# Trefferzonenmodul.net
KiCad netlist of a schematic drawn in EAGLE
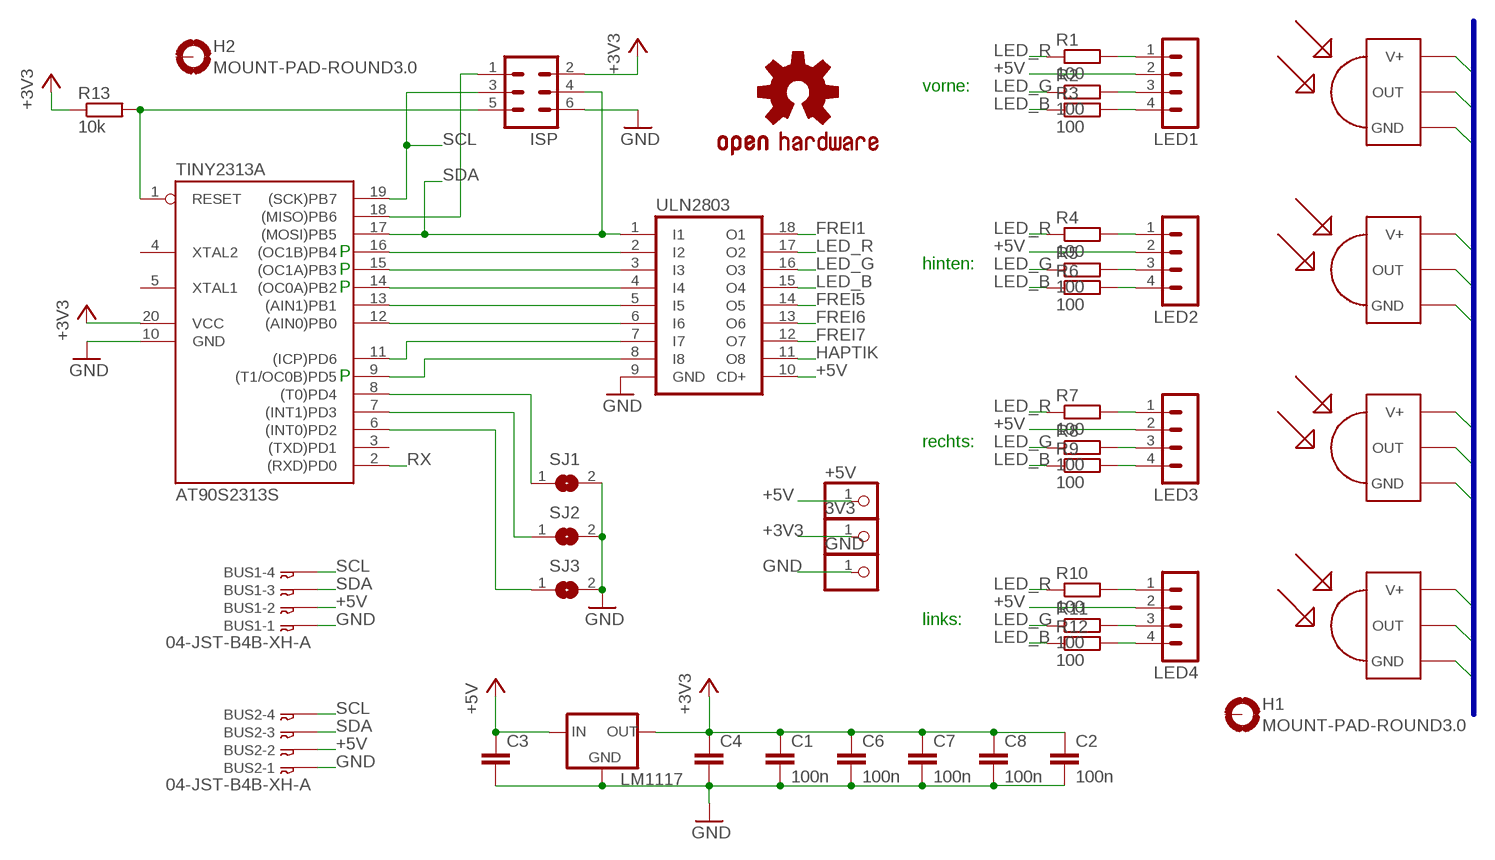
[diagram p0: schematic, sheet 1]

(export (version "E")
  (design (tool "Eeschema 10.0.6"))
  (components
    (comp (ref "+5V")
      (value "PINHD-1X1")
      (footprint "eagle-import:1X01")
      (libsource (lib "eagle-import") (part "PINHD-1X1"))
    )
    (comp (ref "3V3")
      (value "PINHD-1X1")
      (footprint "eagle-import:1X01")
      (libsource (lib "eagle-import") (part "PINHD-1X1"))
    )
    (comp (ref "BUS1")
      (value "04-JST-B4B-XH-A")
      (footprint "eagle-import:B4B-XH")
      (libsource (lib "eagle-import") (part "04-JST-B4B-XH-A"))
    )
    (comp (ref "BUS2")
      (value "04-JST-B4B-XH-A")
      (footprint "eagle-import:B4B-XH")
      (libsource (lib "eagle-import") (part "04-JST-B4B-XH-A"))
    )
    (comp (ref "C1")
      (value "100n")
      (footprint "eagle-import:C0805")
      (libsource (lib "eagle-import") (part "C-EUC0805"))
    )
    (comp (ref "C2")
      (value "100n")
      (footprint "eagle-import:C0805")
      (libsource (lib "eagle-import") (part "C-EUC0805"))
    )
    (comp (ref "C3")
      (value "C-EUCAP_UNIVERSAL")
      (footprint "eagle-import:C1808")
      (libsource (lib "eagle-import") (part "C-EUCAP_UNIVERSAL"))
    )
    (comp (ref "C4")
      (value "C-EUCAP_UNIVERSAL")
      (footprint "eagle-import:C1808")
      (libsource (lib "eagle-import") (part "C-EUCAP_UNIVERSAL"))
    )
    (comp (ref "C6")
      (value "100n")
      (footprint "eagle-import:C0805")
      (libsource (lib "eagle-import") (part "C-EUC0805"))
    )
    (comp (ref "C7")
      (value "100n")
      (footprint "eagle-import:C0805")
      (libsource (lib "eagle-import") (part "C-EUC0805"))
    )
    (comp (ref "C8")
      (value "100n")
      (footprint "eagle-import:C0805")
      (libsource (lib "eagle-import") (part "C-EUC0805"))
    )
    (comp (ref "GND")
      (value "PINHD-1X1")
      (footprint "eagle-import:1X01")
      (libsource (lib "eagle-import") (part "PINHD-1X1"))
    )
    (comp (ref "H1")
      (value "MOUNT-PAD-ROUND3.0")
      (footprint "eagle-import:3,0-PAD")
      (libsource (lib "eagle-import") (part "MOUNT-PAD-ROUND3.0"))
    )
    (comp (ref "H2")
      (value "MOUNT-PAD-ROUND3.0")
      (footprint "eagle-import:3,0-PAD")
      (libsource (lib "eagle-import") (part "MOUNT-PAD-ROUND3.0"))
    )
    (comp (ref "ISP")
      (value "MA03-2")
      (footprint "eagle-import:MA03-2")
      (libsource (lib "eagle-import") (part "MA03-2"))
    )
    (comp (ref "LED1")
      (value "MA04-1")
      (footprint "eagle-import:MA04-1")
      (libsource (lib "eagle-import") (part "MA04-1"))
    )
    (comp (ref "LED2")
      (value "MA04-1")
      (footprint "eagle-import:MA04-1")
      (libsource (lib "eagle-import") (part "MA04-1"))
    )
    (comp (ref "LED3")
      (value "MA04-1")
      (footprint "eagle-import:MA04-1")
      (libsource (lib "eagle-import") (part "MA04-1"))
    )
    (comp (ref "LED4")
      (value "MA04-1")
      (footprint "eagle-import:MA04-1")
      (libsource (lib "eagle-import") (part "MA04-1"))
    )
    (comp (ref "LM1117")
      (value "V_REG_MIC2920")
      (footprint "eagle-import:SOT223")
      (libsource (lib "eagle-import") (part "V_REG_MIC2920"))
    )
    (comp (ref "LOGO2")
      (value "OSHW-LOGOM")
      (footprint "eagle-import:OSHW-LOGO-M")
      (libsource (lib "eagle-import") (part "OSHW-LOGOM"))
    )
    (comp (ref "R1")
      (value "100")
      (footprint "eagle-import:R0805")
      (libsource (lib "eagle-import") (part "R-EU_R0805"))
    )
    (comp (ref "R2")
      (value "100")
      (footprint "eagle-import:R0805")
      (libsource (lib "eagle-import") (part "R-EU_R0805"))
    )
    (comp (ref "R3")
      (value "100")
      (footprint "eagle-import:R0805")
      (libsource (lib "eagle-import") (part "R-EU_R0805"))
    )
    (comp (ref "R4")
      (value "100")
      (footprint "eagle-import:R0805")
      (libsource (lib "eagle-import") (part "R-EU_R0805"))
    )
    (comp (ref "R5")
      (value "100")
      (footprint "eagle-import:R0805")
      (libsource (lib "eagle-import") (part "R-EU_R0805"))
    )
    (comp (ref "R6")
      (value "100")
      (footprint "eagle-import:R0805")
      (libsource (lib "eagle-import") (part "R-EU_R0805"))
    )
    (comp (ref "R7")
      (value "100")
      (footprint "eagle-import:R0805")
      (libsource (lib "eagle-import") (part "R-EU_R0805"))
    )
    (comp (ref "R8")
      (value "100")
      (footprint "eagle-import:R0805")
      (libsource (lib "eagle-import") (part "R-EU_R0805"))
    )
    (comp (ref "R9")
      (value "100")
      (footprint "eagle-import:R0805")
      (libsource (lib "eagle-import") (part "R-EU_R0805"))
    )
    (comp (ref "R10")
      (value "100")
      (footprint "eagle-import:R0805")
      (libsource (lib "eagle-import") (part "R-EU_R0805"))
    )
    (comp (ref "R11")
      (value "100")
      (footprint "eagle-import:R0805")
      (libsource (lib "eagle-import") (part "R-EU_R0805"))
    )
    (comp (ref "R12")
      (value "100")
      (footprint "eagle-import:R0805")
      (libsource (lib "eagle-import") (part "R-EU_R0805"))
    )
    (comp (ref "R13")
      (value "10k")
      (footprint "eagle-import:R0805")
      (libsource (lib "eagle-import") (part "R-EU_R0805"))
    )
    (comp (ref "SJ1") (value "SJ") (footprint "eagle-import:SJ") (libsource (lib "eagle-import") (part "SJ")))
    (comp (ref "SJ2") (value "SJ") (footprint "eagle-import:SJ") (libsource (lib "eagle-import") (part "SJ")))
    (comp (ref "SJ3") (value "SJ") (footprint "eagle-import:SJ") (libsource (lib "eagle-import") (part "SJ")))
    (comp (ref "TINY2313A")
      (value "AT90S2313S")
      (footprint "eagle-import:SO20L")
      (libsource (lib "eagle-import") (part "AT90S2313S"))
    )
    (comp (ref "U$1")
      (value "TSOP1838")
      (footprint "eagle-import:TSOP18XX")
      (libsource (lib "eagle-import") (part "TSOP1838"))
    )
    (comp (ref "U$2")
      (value "TSOP1838")
      (footprint "eagle-import:TSOP18XX")
      (libsource (lib "eagle-import") (part "TSOP1838"))
    )
    (comp (ref "U$3")
      (value "TSOP1838")
      (footprint "eagle-import:TSOP18XX")
      (libsource (lib "eagle-import") (part "TSOP1838"))
    )
    (comp (ref "U$4")
      (value "TSOP1838")
      (footprint "eagle-import:TSOP18XX")
      (libsource (lib "eagle-import") (part "TSOP1838"))
    )
    (comp (ref "ULN2803")
      (value "ULN2803ASO18")
      (footprint "eagle-import:SO18W")
      (libsource (lib "eagle-import") (part "ULN2803ASO18"))
    )
  )
  (nets
    (net (code "1") (name "+3V3") (class "Default")
      (node (ref "3V3") (pin "1") (pinfunction "1_1") (pintype "passive"))
      (node (ref "C1") (pin "1") (pinfunction "1_1") (pintype "passive"))
      (node (ref "C2") (pin "1") (pinfunction "1_1") (pintype "passive"))
      (node (ref "C4") (pin "1") (pinfunction "1_1") (pintype "passive"))
      (node (ref "C6") (pin "1") (pinfunction "1_1") (pintype "passive"))
      (node (ref "C7") (pin "1") (pinfunction "1_1") (pintype "passive"))
      (node (ref "C8") (pin "1") (pinfunction "1_1") (pintype "passive"))
      (node (ref "ISP") (pin "2") (pinfunction "2_2") (pintype "passive"))
      (node (ref "LM1117") (pin "2") (pinfunction "OUT_2") (pintype "passive"))
      (node (ref "LM1117") (pin "4") (pinfunction "OUT_4") (pintype "passive"))
      (node (ref "R13") (pin "1") (pinfunction "1_1") (pintype "passive"))
      (node (ref "TINY2313A") (pin "20") (pinfunction "VCC_20") (pintype "power_in"))
      (node (ref "U$1") (pin "VCC") (pinfunction "V+_VCC") (pintype "bidirectional"))
      (node (ref "U$2") (pin "VCC") (pinfunction "V+_VCC") (pintype "bidirectional"))
      (node (ref "U$3") (pin "VCC") (pinfunction "V+_VCC") (pintype "bidirectional"))
      (node (ref "U$4") (pin "VCC") (pinfunction "V+_VCC") (pintype "bidirectional"))
    )
    (net (code "2") (name "+5V") (class "Default")
      (node (ref "+5V") (pin "1") (pinfunction "1_1") (pintype "passive"))
      (node (ref "BUS1") (pin "P$2") (pinfunction "1_P$2") (pintype "passive"))
      (node (ref "BUS2") (pin "P$2") (pinfunction "1_P$2") (pintype "passive"))
      (node (ref "C3") (pin "1") (pinfunction "1_1") (pintype "passive"))
      (node (ref "LED1") (pin "2") (pinfunction "2_2") (pintype "passive"))
      (node (ref "LED2") (pin "2") (pinfunction "2_2") (pintype "passive"))
      (node (ref "LED3") (pin "2") (pinfunction "2_2") (pintype "passive"))
      (node (ref "LED4") (pin "2") (pinfunction "2_2") (pintype "passive"))
      (node (ref "LM1117") (pin "3") (pinfunction "IN_3") (pintype "input"))
      (node (ref "ULN2803") (pin "10") (pinfunction "CD+_10") (pintype "passive"))
    )
    (net (code "3") (name "/FREI1") (class "Default")
      (node (ref "ULN2803") (pin "18") (pinfunction "O1_18") (pintype "open_collector"))
    )
    (net (code "4") (name "/FREI5") (class "Default")
      (node (ref "ULN2803") (pin "14") (pinfunction "O5_14") (pintype "open_collector"))
    )
    (net (code "5") (name "/FREI6") (class "Default")
      (node (ref "ULN2803") (pin "13") (pinfunction "O6_13") (pintype "open_collector"))
    )
    (net (code "6") (name "/FREI7") (class "Default")
      (node (ref "ULN2803") (pin "12") (pinfunction "O7_12") (pintype "open_collector"))
    )
    (net (code "7") (name "/HAPTIK") (class "Default")
      (node (ref "ULN2803") (pin "11") (pinfunction "O8_11") (pintype "open_collector"))
    )
    (net (code "8") (name "/LED_B") (class "Default")
      (node (ref "R12") (pin "1") (pinfunction "1_1") (pintype "passive"))
      (node (ref "R3") (pin "1") (pinfunction "1_1") (pintype "passive"))
      (node (ref "R6") (pin "1") (pinfunction "1_1") (pintype "passive"))
      (node (ref "R9") (pin "1") (pinfunction "1_1") (pintype "passive"))
      (node (ref "ULN2803") (pin "15") (pinfunction "O4_15") (pintype "open_collector"))
    )
    (net (code "9") (name "/LED_G") (class "Default")
      (node (ref "R11") (pin "1") (pinfunction "1_1") (pintype "passive"))
      (node (ref "R2") (pin "1") (pinfunction "1_1") (pintype "passive"))
      (node (ref "R5") (pin "1") (pinfunction "1_1") (pintype "passive"))
      (node (ref "R8") (pin "1") (pinfunction "1_1") (pintype "passive"))
      (node (ref "ULN2803") (pin "16") (pinfunction "O3_16") (pintype "open_collector"))
    )
    (net (code "10") (name "/LED_R") (class "Default")
      (node (ref "R1") (pin "1") (pinfunction "1_1") (pintype "passive"))
      (node (ref "R10") (pin "1") (pinfunction "1_1") (pintype "passive"))
      (node (ref "R4") (pin "1") (pinfunction "1_1") (pintype "passive"))
      (node (ref "R7") (pin "1") (pinfunction "1_1") (pintype "passive"))
      (node (ref "ULN2803") (pin "17") (pinfunction "O2_17") (pintype "open_collector"))
    )
    (net (code "11") (name "/RX") (class "Default")
      (node (ref "TINY2313A") (pin "2") (pinfunction "(RXD)PD0_2") (pintype "bidirectional"))
      (node (ref "U$1") (pin "OUT") (pinfunction "OUT_OUT") (pintype "bidirectional"))
      (node (ref "U$2") (pin "OUT") (pinfunction "OUT_OUT") (pintype "bidirectional"))
      (node (ref "U$3") (pin "OUT") (pinfunction "OUT_OUT") (pintype "bidirectional"))
      (node (ref "U$4") (pin "OUT") (pinfunction "OUT_OUT") (pintype "bidirectional"))
    )
    (net (code "12") (name "/SCL") (class "Default")
      (node (ref "BUS1") (pin "P$4") (pinfunction "1_P$4") (pintype "passive"))
      (node (ref "BUS2") (pin "P$4") (pinfunction "1_P$4") (pintype "passive"))
      (node (ref "ISP") (pin "3") (pinfunction "3_3") (pintype "passive"))
      (node (ref "TINY2313A") (pin "19") (pinfunction "(SCK)PB7_19") (pintype "bidirectional"))
    )
    (net (code "13") (name "/SDA") (class "Default")
      (node (ref "BUS1") (pin "P$3") (pinfunction "1_P$3") (pintype "passive"))
      (node (ref "BUS2") (pin "P$3") (pinfunction "1_P$3") (pintype "passive"))
      (node (ref "ISP") (pin "4") (pinfunction "4_4") (pintype "passive"))
      (node (ref "TINY2313A") (pin "17") (pinfunction "(MOSI)PB5_17") (pintype "bidirectional"))
      (node (ref "ULN2803") (pin "1") (pinfunction "I1_1") (pintype "input"))
    )
    (net (code "14") (name "GND") (class "Default")
      (node (ref "BUS1") (pin "P$1") (pinfunction "1_P$1") (pintype "passive"))
      (node (ref "BUS2") (pin "P$1") (pinfunction "1_P$1") (pintype "passive"))
      (node (ref "C1") (pin "2") (pinfunction "2_2") (pintype "passive"))
      (node (ref "C2") (pin "2") (pinfunction "2_2") (pintype "passive"))
      (node (ref "C3") (pin "2") (pinfunction "2_2") (pintype "passive"))
      (node (ref "C4") (pin "2") (pinfunction "2_2") (pintype "passive"))
      (node (ref "C6") (pin "2") (pinfunction "2_2") (pintype "passive"))
      (node (ref "C7") (pin "2") (pinfunction "2_2") (pintype "passive"))
      (node (ref "C8") (pin "2") (pinfunction "2_2") (pintype "passive"))
      (node (ref "GND") (pin "1") (pinfunction "1_1") (pintype "passive"))
      (node (ref "ISP") (pin "6") (pinfunction "6_6") (pintype "passive"))
      (node (ref "LM1117") (pin "1") (pinfunction "GND_1") (pintype "input"))
      (node (ref "SJ1") (pin "2") (pinfunction "2_2") (pintype "passive"))
      (node (ref "SJ2") (pin "2") (pinfunction "2_2") (pintype "passive"))
      (node (ref "SJ3") (pin "2") (pinfunction "2_2") (pintype "passive"))
      (node (ref "TINY2313A") (pin "10") (pinfunction "GND_10") (pintype "power_in"))
      (node (ref "U$1") (pin "GND") (pinfunction "GND_GND") (pintype "bidirectional"))
      (node (ref "U$2") (pin "GND") (pinfunction "GND_GND") (pintype "bidirectional"))
      (node (ref "U$3") (pin "GND") (pinfunction "GND_GND") (pintype "bidirectional"))
      (node (ref "U$4") (pin "GND") (pinfunction "GND_GND") (pintype "bidirectional"))
      (node (ref "ULN2803") (pin "9") (pinfunction "GND_9") (pintype "power_in"))
    )
    (net (code "15") (name "Net-(LED1-Pad1)") (class "Default")
      (node (ref "LED1") (pin "1") (pinfunction "1_1") (pintype "passive"))
      (node (ref "R1") (pin "2") (pinfunction "2_2") (pintype "passive"))
    )
    (net (code "16") (name "Net-(LED1-Pad3)") (class "Default")
      (node (ref "LED1") (pin "3") (pinfunction "3_3") (pintype "passive"))
      (node (ref "R2") (pin "2") (pinfunction "2_2") (pintype "passive"))
    )
    (net (code "17") (name "Net-(LED1-Pad4)") (class "Default")
      (node (ref "LED1") (pin "4") (pinfunction "4_4") (pintype "passive"))
      (node (ref "R3") (pin "2") (pinfunction "2_2") (pintype "passive"))
    )
    (net (code "18") (name "Net-(LED2-Pad1)") (class "Default")
      (node (ref "LED2") (pin "1") (pinfunction "1_1") (pintype "passive"))
      (node (ref "R4") (pin "2") (pinfunction "2_2") (pintype "passive"))
    )
    (net (code "19") (name "Net-(LED2-Pad3)") (class "Default")
      (node (ref "LED2") (pin "3") (pinfunction "3_3") (pintype "passive"))
      (node (ref "R5") (pin "2") (pinfunction "2_2") (pintype "passive"))
    )
    (net (code "20") (name "Net-(LED2-Pad4)") (class "Default")
      (node (ref "LED2") (pin "4") (pinfunction "4_4") (pintype "passive"))
      (node (ref "R6") (pin "2") (pinfunction "2_2") (pintype "passive"))
    )
    (net (code "21") (name "Net-(LED3-Pad1)") (class "Default")
      (node (ref "LED3") (pin "1") (pinfunction "1_1") (pintype "passive"))
      (node (ref "R7") (pin "2") (pinfunction "2_2") (pintype "passive"))
    )
    (net (code "22") (name "Net-(LED3-Pad3)") (class "Default")
      (node (ref "LED3") (pin "3") (pinfunction "3_3") (pintype "passive"))
      (node (ref "R8") (pin "2") (pinfunction "2_2") (pintype "passive"))
    )
    (net (code "23") (name "Net-(LED3-Pad4)") (class "Default")
      (node (ref "LED3") (pin "4") (pinfunction "4_4") (pintype "passive"))
      (node (ref "R9") (pin "2") (pinfunction "2_2") (pintype "passive"))
    )
    (net (code "24") (name "Net-(LED4-Pad1)") (class "Default")
      (node (ref "LED4") (pin "1") (pinfunction "1_1") (pintype "passive"))
      (node (ref "R10") (pin "2") (pinfunction "2_2") (pintype "passive"))
    )
    (net (code "25") (name "Net-(LED4-Pad3)") (class "Default")
      (node (ref "LED4") (pin "3") (pinfunction "3_3") (pintype "passive"))
      (node (ref "R11") (pin "2") (pinfunction "2_2") (pintype "passive"))
    )
    (net (code "26") (name "Net-(LED4-Pad4)") (class "Default")
      (node (ref "LED4") (pin "4") (pinfunction "4_4") (pintype "passive"))
      (node (ref "R12") (pin "2") (pinfunction "2_2") (pintype "passive"))
    )
    (net (code "27") (name "Net-(TINY2313A-(AIN0)PB0)") (class "Default")
      (node (ref "TINY2313A") (pin "12") (pinfunction "(AIN0)PB0_12") (pintype "bidirectional"))
      (node (ref "ULN2803") (pin "6") (pinfunction "I6_6") (pintype "input"))
    )
    (net (code "28") (name "Net-(TINY2313A-(AIN1)PB1)") (class "Default")
      (node (ref "TINY2313A") (pin "13") (pinfunction "(AIN1)PB1_13") (pintype "bidirectional"))
      (node (ref "ULN2803") (pin "5") (pinfunction "I5_5") (pintype "input"))
    )
    (net (code "29") (name "Net-(TINY2313A-(ICP)PD6)") (class "Default")
      (node (ref "TINY2313A") (pin "11") (pinfunction "(ICP)PD6_11") (pintype "bidirectional"))
      (node (ref "ULN2803") (pin "7") (pinfunction "I7_7") (pintype "input"))
    )
    (net (code "30") (name "Net-(TINY2313A-(INT0)PD2)") (class "Default")
      (node (ref "SJ3") (pin "1") (pinfunction "1_1") (pintype "passive"))
      (node (ref "TINY2313A") (pin "6") (pinfunction "(INT0)PD2_6") (pintype "bidirectional"))
    )
    (net (code "31") (name "Net-(TINY2313A-(INT1)PD3)") (class "Default")
      (node (ref "SJ2") (pin "1") (pinfunction "1_1") (pintype "passive"))
      (node (ref "TINY2313A") (pin "7") (pinfunction "(INT1)PD3_7") (pintype "bidirectional"))
    )
    (net (code "32") (name "Net-(TINY2313A-(MISO)PB6)") (class "Default")
      (node (ref "ISP") (pin "1") (pinfunction "1_1") (pintype "passive"))
      (node (ref "TINY2313A") (pin "18") (pinfunction "(MISO)PB6_18") (pintype "bidirectional"))
    )
    (net (code "33") (name "Net-(TINY2313A-(OC0A)PB2)") (class "Default")
      (node (ref "TINY2313A") (pin "14") (pinfunction "(OC0A)PB2_14") (pintype "bidirectional"))
      (node (ref "ULN2803") (pin "4") (pinfunction "I4_4") (pintype "input"))
    )
    (net (code "34") (name "Net-(TINY2313A-(OC1A)PB3)") (class "Default")
      (node (ref "TINY2313A") (pin "15") (pinfunction "(OC1A)PB3_15") (pintype "bidirectional"))
      (node (ref "ULN2803") (pin "3") (pinfunction "I3_3") (pintype "input"))
    )
    (net (code "35") (name "Net-(TINY2313A-(OC1B)PB4)") (class "Default")
      (node (ref "TINY2313A") (pin "16") (pinfunction "(OC1B)PB4_16") (pintype "bidirectional"))
      (node (ref "ULN2803") (pin "2") (pinfunction "I2_2") (pintype "input"))
    )
    (net (code "36") (name "Net-(TINY2313A-(T0)PD4)") (class "Default")
      (node (ref "SJ1") (pin "1") (pinfunction "1_1") (pintype "passive"))
      (node (ref "TINY2313A") (pin "8") (pinfunction "(T0)PD4_8") (pintype "bidirectional"))
    )
    (net (code "37") (name "Net-(TINY2313A-(T1{slash}OC0B)PD5)") (class "Default")
      (node (ref "TINY2313A") (pin "9") (pinfunction "(T1/OC0B)PD5_9") (pintype "bidirectional"))
      (node (ref "ULN2803") (pin "8") (pinfunction "I8_8") (pintype "input"))
    )
    (net (code "38") (name "Net-(TINY2313A-RESET)") (class "Default")
      (node (ref "ISP") (pin "5") (pinfunction "5_5") (pintype "passive"))
      (node (ref "R13") (pin "2") (pinfunction "2_2") (pintype "passive"))
      (node (ref "TINY2313A") (pin "1") (pinfunction "RESET_1") (pintype "bidirectional"))
    )
    (net (code "39") (name "unconnected-(H1-MOUNT-PadB3,0)") (class "Default")
      (node (ref "H1") (pin "B3,0") (pinfunction "MOUNT_B3,0") (pintype "passive"))
    )
    (net (code "40") (name "unconnected-(H2-MOUNT-PadB3,0)") (class "Default")
      (node (ref "H2") (pin "B3,0") (pinfunction "MOUNT_B3,0") (pintype "passive"))
    )
    (net (code "41") (name "unconnected-(TINY2313A-(TXD)PD1-Pad3)") (class "Default")
      (node (ref "TINY2313A") (pin "3") (pinfunction "(TXD)PD1_3") (pintype "bidirectional"))
    )
    (net (code "42") (name "unconnected-(TINY2313A-XTAL1-Pad5)") (class "Default")
      (node (ref "TINY2313A") (pin "5") (pinfunction "XTAL1_5") (pintype "bidirectional"))
    )
    (net (code "43") (name "unconnected-(TINY2313A-XTAL2-Pad4)") (class "Default")
      (node (ref "TINY2313A") (pin "4") (pinfunction "XTAL2_4") (pintype "bidirectional"))
    )
  )
)
